# esp8266-hw8.net
KiCad netlist of a schematic drawn in EAGLE
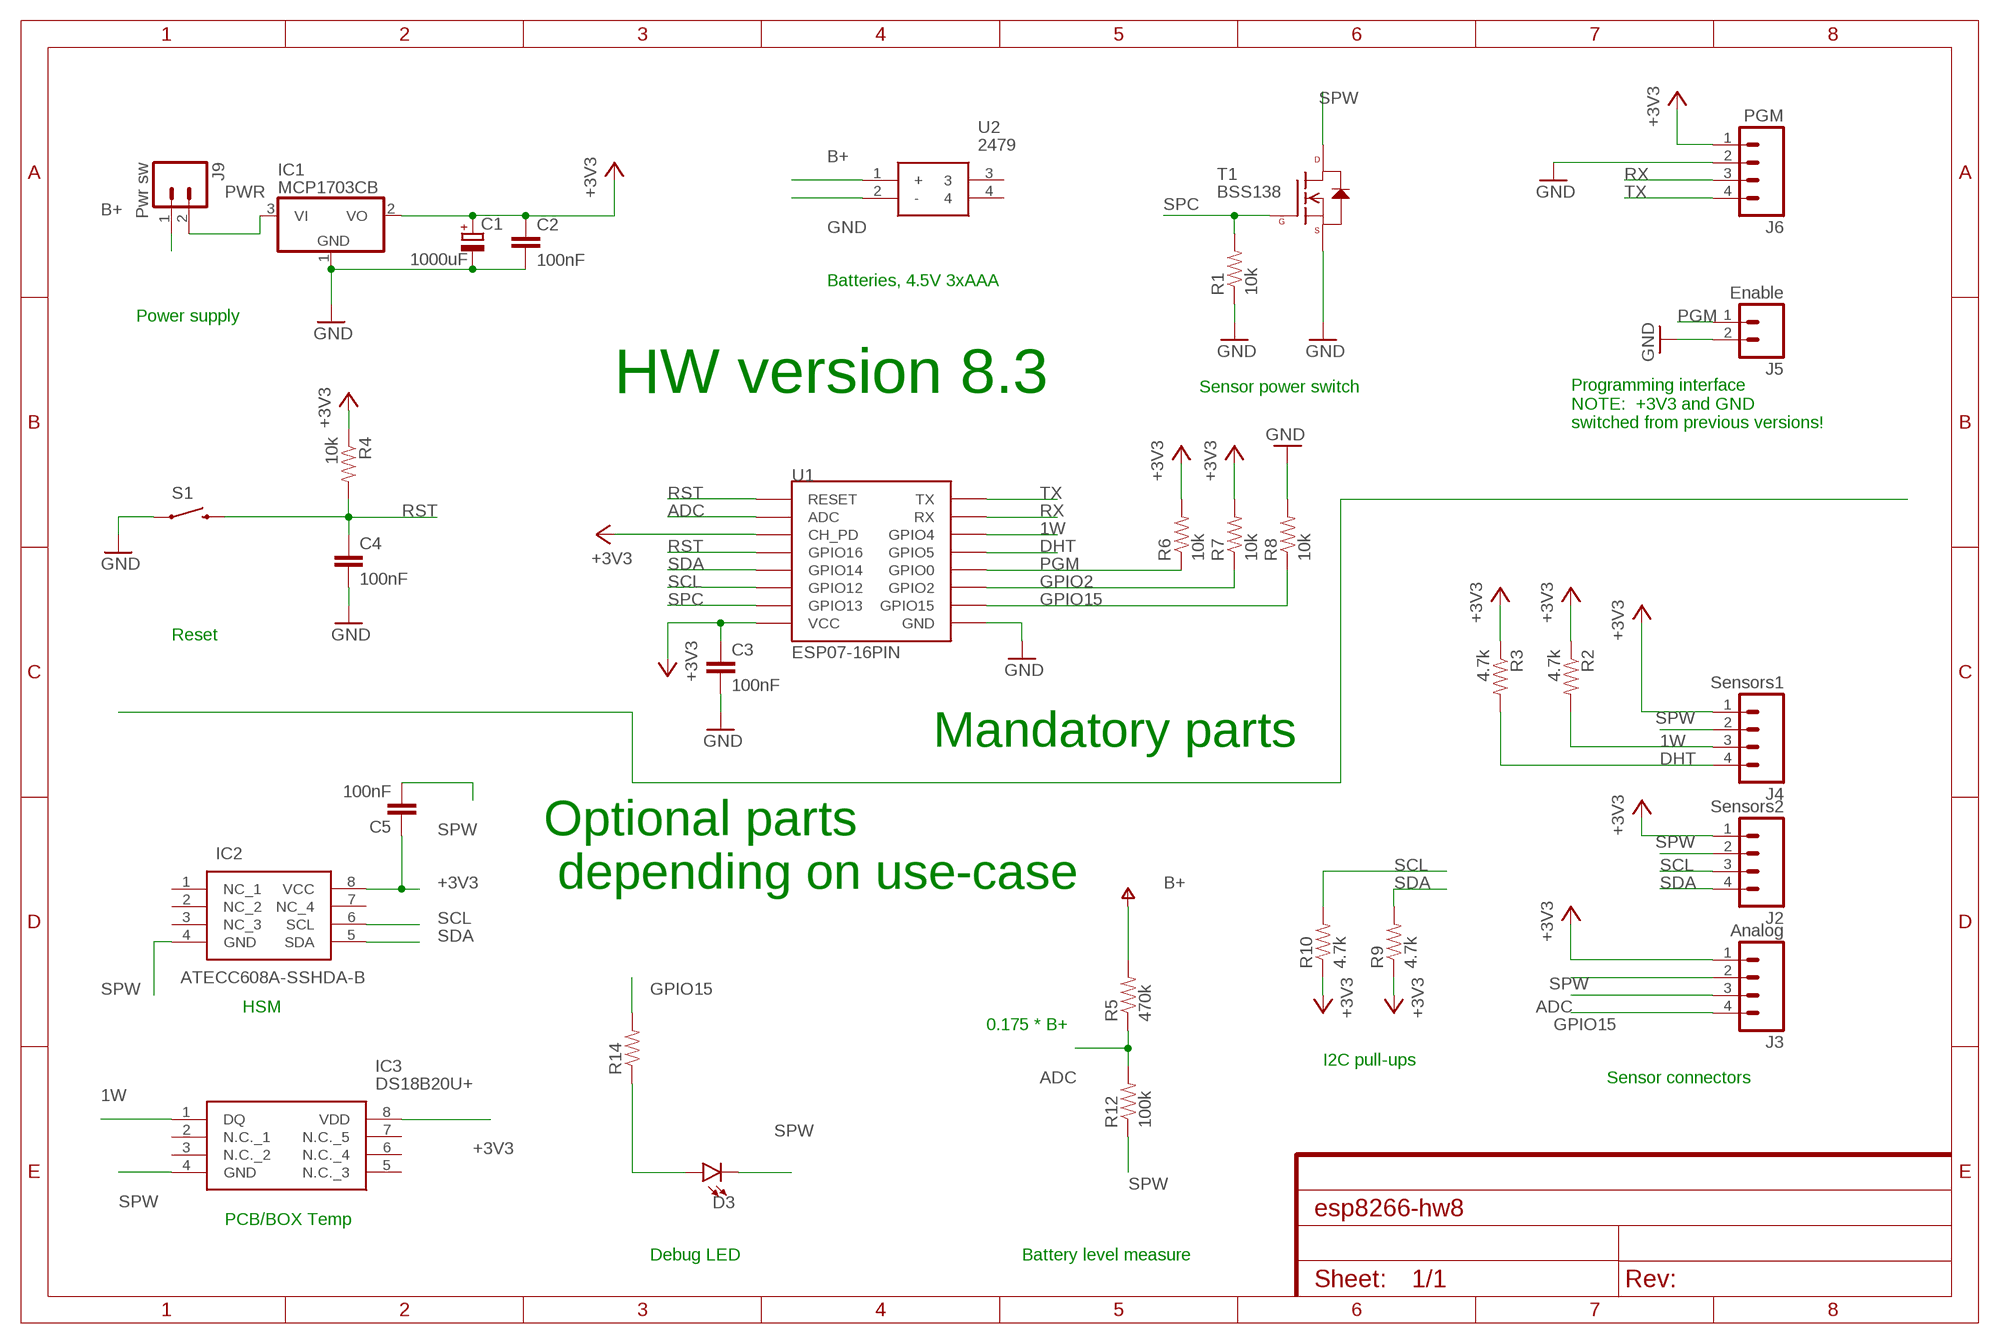
[diagram p0: schematic, sheet 1]

(export (version "E")
  (design (tool "Eeschema 10.0.6"))
  (components
    (comp (ref "C1")
      (value "1000uF")
      (footprint "eagle-import:E3,5-8")
      (libsource (lib "eagle-import") (part "CPOL-EUE3.5-8"))
    )
    (comp (ref "C2")
      (value "100nF")
      (footprint "eagle-import:0805")
      (libsource (lib "eagle-import") (part "CAP0805"))
    )
    (comp (ref "C3")
      (value "100nF")
      (footprint "eagle-import:0805")
      (libsource (lib "eagle-import") (part "CAP0805"))
    )
    (comp (ref "C4")
      (value "100nF")
      (footprint "eagle-import:0805")
      (libsource (lib "eagle-import") (part "CAP0805"))
    )
    (comp (ref "C5")
      (value "100nF")
      (footprint "eagle-import:0805")
      (libsource (lib "eagle-import") (part "CAP0805"))
    )
    (comp (ref "D3")
      (value "LED3MM")
      (footprint "eagle-import:LED_3MM")
      (libsource (lib "eagle-import") (part "LED3MM"))
    )
    (comp (ref "IC1")
      (value "MCP1703CB")
      (footprint "eagle-import:SOT23")
      (libsource (lib "eagle-import") (part "MCP1703CB"))
    )
    (comp (ref "IC2")
      (value "ATECC608A-SSHDA-B")
      (footprint "eagle-import:SOIC127P600X175-8N")
      (fields (field (name "MOUSER_PART_NUMBER") "556-ATECC608ASSHDAB"))
      (libsource (lib "eagle-import") (part "ATECC608A-SSHDA-B"))
    )
    (comp (ref "IC3")
      (value "DS18B20U+")
      (footprint "eagle-import:SOP65P490X110-8N")
      (fields (field (name "MOUSER_PART_NUMBER") "700-DS18B20U"))
      (libsource (lib "eagle-import") (part "DS18B20U+"))
    )
    (comp (ref "J2")
      (value "Sensors2")
      (footprint "eagle-import:1X04")
      (libsource (lib "eagle-import") (part "M04PTH"))
    )
    (comp (ref "J3")
      (value "Analog")
      (footprint "eagle-import:1X04")
      (libsource (lib "eagle-import") (part "M04PTH"))
    )
    (comp (ref "J4")
      (value "Sensors1")
      (footprint "eagle-import:1X04")
      (libsource (lib "eagle-import") (part "M04PTH"))
    )
    (comp (ref "J5")
      (value "Enable")
      (footprint "eagle-import:1X02")
      (libsource (lib "eagle-import") (part "M02PTH"))
    )
    (comp (ref "J6")
      (value "PGM")
      (footprint "eagle-import:1X04")
      (libsource (lib "eagle-import") (part "M04PTH"))
    )
    (comp (ref "J9")
      (value "Pwr sw")
      (footprint "eagle-import:1X02")
      (libsource (lib "eagle-import") (part "M02PTH"))
    )
    (comp (ref "R1")
      (value "10k")
      (footprint "eagle-import:0805")
      (libsource (lib "eagle-import") (part "RESISTOR0805-RES"))
    )
    (comp (ref "R2")
      (value "4.7k")
      (footprint "eagle-import:0805")
      (libsource (lib "eagle-import") (part "RESISTOR0805-RES"))
    )
    (comp (ref "R3")
      (value "4.7k")
      (footprint "eagle-import:0805")
      (libsource (lib "eagle-import") (part "RESISTOR0805-RES"))
    )
    (comp (ref "R4")
      (value "10k")
      (footprint "eagle-import:0805")
      (libsource (lib "eagle-import") (part "RESISTOR0805-RES"))
    )
    (comp (ref "R5")
      (value "470k")
      (footprint "eagle-import:0805")
      (libsource (lib "eagle-import") (part "RESISTOR0805-RES"))
    )
    (comp (ref "R6")
      (value "10k")
      (footprint "eagle-import:0805")
      (libsource (lib "eagle-import") (part "RESISTOR0805-RES"))
    )
    (comp (ref "R7")
      (value "10k")
      (footprint "eagle-import:0805")
      (libsource (lib "eagle-import") (part "RESISTOR0805-RES"))
    )
    (comp (ref "R8")
      (value "10k")
      (footprint "eagle-import:0805")
      (libsource (lib "eagle-import") (part "RESISTOR0805-RES"))
    )
    (comp (ref "R9")
      (value "4.7k")
      (footprint "eagle-import:0805")
      (libsource (lib "eagle-import") (part "RESISTOR0805-RES"))
    )
    (comp (ref "R10")
      (value "4.7k")
      (footprint "eagle-import:0805")
      (libsource (lib "eagle-import") (part "RESISTOR0805-RES"))
    )
    (comp (ref "R12")
      (value "100k")
      (footprint "eagle-import:0805")
      (libsource (lib "eagle-import") (part "RESISTOR0805-RES"))
    )
    (comp (ref "R14")
      (value "470")
      (footprint "eagle-import:0805")
      (libsource (lib "eagle-import") (part "RESISTOR0805-RES"))
    )
    (comp (ref "S1")
      (value "RESET")
      (footprint "eagle-import:TACTILE-SWITCH-1101NE")
      (libsource (lib "eagle-import") (part "SWITCH-MOMENTARY-2SMD-1101NE"))
    )
    (comp (ref "T1")
      (value "BSS138")
      (footprint "eagle-import:SOT23-3")
      (libsource (lib "eagle-import") (part "N-CHANNEL-MOSFET-BSS138"))
    )
    (comp (ref "U1")
      (value "ESP07-16PIN")
      (footprint "eagle-import:ESP07-16PIN")
      (libsource (lib "eagle-import") (part "ESP07-16PIN"))
    )
    (comp (ref "U2")
      (value "2479")
      (footprint "eagle-import:2479")
      (fields (field (name "MOUSER_PART_NUMBER") "534-2479"))
      (libsource (lib "eagle-import") (part "2479"))
    )
  )
  (nets
    (net (code "1") (name "+3V3") (class "Default")
      (node (ref "C1") (pin "+") (pinfunction "+_+") (pintype "passive"))
      (node (ref "C2") (pin "1") (pinfunction "1_1") (pintype "passive"))
      (node (ref "C3") (pin "1") (pinfunction "1_1") (pintype "passive"))
      (node (ref "C5") (pin "1") (pinfunction "1_1") (pintype "passive"))
      (node (ref "IC1") (pin "2") (pinfunction "VO_2") (pintype "passive"))
      (node (ref "IC2") (pin "8") (pinfunction "VCC_8") (pintype "bidirectional"))
      (node (ref "IC3") (pin "8") (pinfunction "VDD_8") (pintype "power_in"))
      (node (ref "J2") (pin "1") (pinfunction "1_1") (pintype "passive"))
      (node (ref "J3") (pin "1") (pinfunction "1_1") (pintype "passive"))
      (node (ref "J4") (pin "1") (pinfunction "1_1") (pintype "passive"))
      (node (ref "J6") (pin "1") (pinfunction "1_1") (pintype "passive"))
      (node (ref "R10") (pin "1") (pinfunction "1_1") (pintype "passive"))
      (node (ref "R2") (pin "1") (pinfunction "1_1") (pintype "passive"))
      (node (ref "R3") (pin "1") (pinfunction "1_1") (pintype "passive"))
      (node (ref "R4") (pin "1") (pinfunction "1_1") (pintype "passive"))
      (node (ref "R6") (pin "2") (pinfunction "2_2") (pintype "passive"))
      (node (ref "R7") (pin "2") (pinfunction "2_2") (pintype "passive"))
      (node (ref "R9") (pin "1") (pinfunction "1_1") (pintype "passive"))
      (node (ref "U1") (pin "CH_PD") (pinfunction "CH_PD_CH_PD") (pintype "bidirectional"))
      (node (ref "U1") (pin "VCC") (pinfunction "VCC_VCC") (pintype "bidirectional"))
    )
    (net (code "2") (name "/1W") (class "Default")
      (node (ref "IC3") (pin "1") (pinfunction "DQ_1") (pintype "bidirectional"))
      (node (ref "J4") (pin "3") (pinfunction "3_3") (pintype "passive"))
      (node (ref "R2") (pin "2") (pinfunction "2_2") (pintype "passive"))
      (node (ref "U1") (pin "GPIO4") (pinfunction "GPIO4_GPIO4") (pintype "bidirectional"))
    )
    (net (code "3") (name "/ADC") (class "Default")
      (node (ref "J3") (pin "3") (pinfunction "3_3") (pintype "passive"))
      (node (ref "R12") (pin "2") (pinfunction "2_2") (pintype "passive"))
      (node (ref "R5") (pin "1") (pinfunction "1_1") (pintype "passive"))
      (node (ref "U1") (pin "ADC") (pinfunction "ADC_ADC") (pintype "bidirectional"))
    )
    (net (code "4") (name "/DHT") (class "Default")
      (node (ref "J4") (pin "4") (pinfunction "4_4") (pintype "passive"))
      (node (ref "R3") (pin "2") (pinfunction "2_2") (pintype "passive"))
      (node (ref "U1") (pin "GPIO5") (pinfunction "GPIO5_GPIO5") (pintype "bidirectional"))
    )
    (net (code "5") (name "/GPIO2") (class "Default")
      (node (ref "R7") (pin "1") (pinfunction "1_1") (pintype "passive"))
      (node (ref "U1") (pin "GPIO2") (pinfunction "GPIO2_GPIO2") (pintype "bidirectional"))
    )
    (net (code "6") (name "/GPIO15") (class "Default")
      (node (ref "J3") (pin "4") (pinfunction "4_4") (pintype "passive"))
      (node (ref "R14") (pin "2") (pinfunction "2_2") (pintype "passive"))
      (node (ref "R8") (pin "1") (pinfunction "1_1") (pintype "passive"))
      (node (ref "U1") (pin "GPIO15") (pinfunction "GPIO15_GPIO15") (pintype "bidirectional"))
    )
    (net (code "7") (name "/PGM") (class "Default")
      (node (ref "J5") (pin "1") (pinfunction "1_1") (pintype "passive"))
      (node (ref "R6") (pin "1") (pinfunction "1_1") (pintype "passive"))
      (node (ref "U1") (pin "GPIO0") (pinfunction "GPIO0_GPIO0") (pintype "bidirectional"))
    )
    (net (code "8") (name "/PWR") (class "Default")
      (node (ref "IC1") (pin "3") (pinfunction "VI_3") (pintype "input"))
      (node (ref "J9") (pin "2") (pinfunction "2_2") (pintype "passive"))
    )
    (net (code "9") (name "/RST") (class "Default")
      (node (ref "C4") (pin "1") (pinfunction "1_1") (pintype "passive"))
      (node (ref "R4") (pin "2") (pinfunction "2_2") (pintype "passive"))
      (node (ref "S1") (pin "2") (pinfunction "2_2") (pintype "passive"))
      (node (ref "U1") (pin "GPIO16") (pinfunction "GPIO16_GPIO16") (pintype "bidirectional"))
      (node (ref "U1") (pin "REST") (pinfunction "RESET_REST") (pintype "bidirectional"))
    )
    (net (code "10") (name "/RX") (class "Default")
      (node (ref "J6") (pin "3") (pinfunction "3_3") (pintype "passive"))
      (node (ref "U1") (pin "RX") (pinfunction "RX_RX") (pintype "bidirectional"))
    )
    (net (code "11") (name "/SCL") (class "Default")
      (node (ref "IC2") (pin "6") (pinfunction "SCL_6") (pintype "bidirectional"))
      (node (ref "J2") (pin "3") (pinfunction "3_3") (pintype "passive"))
      (node (ref "R10") (pin "2") (pinfunction "2_2") (pintype "passive"))
      (node (ref "U1") (pin "GPIO12") (pinfunction "GPIO12_GPIO12") (pintype "bidirectional"))
    )
    (net (code "12") (name "/SDA") (class "Default")
      (node (ref "IC2") (pin "5") (pinfunction "SDA_5") (pintype "bidirectional"))
      (node (ref "J2") (pin "4") (pinfunction "4_4") (pintype "passive"))
      (node (ref "R9") (pin "2") (pinfunction "2_2") (pintype "passive"))
      (node (ref "U1") (pin "GPIO14") (pinfunction "GPIO14_GPIO14") (pintype "bidirectional"))
    )
    (net (code "13") (name "/SPC") (class "Default")
      (node (ref "R1") (pin "2") (pinfunction "2_2") (pintype "passive"))
      (node (ref "T1") (pin "1") (pinfunction "G_1") (pintype "passive"))
      (node (ref "U1") (pin "GPIO13") (pinfunction "GPIO13_GPIO13") (pintype "bidirectional"))
    )
    (net (code "14") (name "/SPW") (class "Default")
      (node (ref "C5") (pin "2") (pinfunction "2_2") (pintype "passive"))
      (node (ref "D3") (pin "K") (pinfunction "C_K") (pintype "passive"))
      (node (ref "IC2") (pin "4") (pinfunction "GND_4") (pintype "bidirectional"))
      (node (ref "IC3") (pin "4") (pinfunction "GND_4") (pintype "power_in"))
      (node (ref "J2") (pin "2") (pinfunction "2_2") (pintype "passive"))
      (node (ref "J3") (pin "2") (pinfunction "2_2") (pintype "passive"))
      (node (ref "J4") (pin "2") (pinfunction "2_2") (pintype "passive"))
      (node (ref "R12") (pin "1") (pinfunction "1_1") (pintype "passive"))
      (node (ref "T1") (pin "3") (pinfunction "D_3") (pintype "passive"))
    )
    (net (code "15") (name "/TX") (class "Default")
      (node (ref "J6") (pin "4") (pinfunction "4_4") (pintype "passive"))
      (node (ref "U1") (pin "TX") (pinfunction "TX_TX") (pintype "bidirectional"))
    )
    (net (code "16") (name "GND") (class "Default")
      (node (ref "C1") (pin "-") (pinfunction "-_-") (pintype "passive"))
      (node (ref "C2") (pin "2") (pinfunction "2_2") (pintype "passive"))
      (node (ref "C3") (pin "2") (pinfunction "2_2") (pintype "passive"))
      (node (ref "C4") (pin "2") (pinfunction "2_2") (pintype "passive"))
      (node (ref "IC1") (pin "1") (pinfunction "GND_1") (pintype "passive"))
      (node (ref "J5") (pin "2") (pinfunction "2_2") (pintype "passive"))
      (node (ref "J6") (pin "2") (pinfunction "2_2") (pintype "passive"))
      (node (ref "R1") (pin "1") (pinfunction "1_1") (pintype "passive"))
      (node (ref "R8") (pin "2") (pinfunction "2_2") (pintype "passive"))
      (node (ref "S1") (pin "1") (pinfunction "1_1") (pintype "passive"))
      (node (ref "T1") (pin "2") (pinfunction "S_2") (pintype "passive"))
      (node (ref "U1") (pin "GND") (pinfunction "GND_GND") (pintype "bidirectional"))
      (node (ref "U2") (pin "2") (pinfunction "-_2") (pintype "bidirectional"))
    )
    (net (code "17") (name "Net-(D3-PadA)") (class "Default")
      (node (ref "D3") (pin "A") (pinfunction "A_A") (pintype "passive"))
      (node (ref "R14") (pin "1") (pinfunction "1_1") (pintype "passive"))
    )
    (net (code "18") (name "V+") (class "Default")
      (node (ref "J9") (pin "1") (pinfunction "1_1") (pintype "passive"))
      (node (ref "R5") (pin "2") (pinfunction "2_2") (pintype "passive"))
      (node (ref "U2") (pin "1") (pinfunction "+_1") (pintype "bidirectional"))
    )
    (net (code "19") (name "unconnected-(IC2-NC_1-Pad1)") (class "Default")
      (node (ref "IC2") (pin "1") (pinfunction "NC_1_1") (pintype "bidirectional"))
    )
    (net (code "20") (name "unconnected-(IC2-NC_2-Pad2)") (class "Default")
      (node (ref "IC2") (pin "2") (pinfunction "NC_2_2") (pintype "bidirectional"))
    )
    (net (code "21") (name "unconnected-(IC2-NC_3-Pad3)") (class "Default")
      (node (ref "IC2") (pin "3") (pinfunction "NC_3_3") (pintype "bidirectional"))
    )
    (net (code "22") (name "unconnected-(IC2-NC_4-Pad7)") (class "Default")
      (node (ref "IC2") (pin "7") (pinfunction "NC_4_7") (pintype "bidirectional"))
    )
    (net (code "23") (name "unconnected-(IC3-N.C._1-Pad2)") (class "Default")
      (node (ref "IC3") (pin "2") (pinfunction "N.C._1_2") (pintype "bidirectional"))
    )
    (net (code "24") (name "unconnected-(IC3-N.C._2-Pad3)") (class "Default")
      (node (ref "IC3") (pin "3") (pinfunction "N.C._2_3") (pintype "bidirectional"))
    )
    (net (code "25") (name "unconnected-(IC3-N.C._3-Pad5)") (class "Default")
      (node (ref "IC3") (pin "5") (pinfunction "N.C._3_5") (pintype "bidirectional"))
    )
    (net (code "26") (name "unconnected-(IC3-N.C._4-Pad6)") (class "Default")
      (node (ref "IC3") (pin "6") (pinfunction "N.C._4_6") (pintype "bidirectional"))
    )
    (net (code "27") (name "unconnected-(IC3-N.C._5-Pad7)") (class "Default")
      (node (ref "IC3") (pin "7") (pinfunction "N.C._5_7") (pintype "bidirectional"))
    )
    (net (code "28") (name "unconnected-(U2-Pad3)") (class "Default")
      (node (ref "U2") (pin "3") (pinfunction "3_3") (pintype "bidirectional"))
    )
    (net (code "29") (name "unconnected-(U2-Pad4)") (class "Default")
      (node (ref "U2") (pin "4") (pinfunction "4_4") (pintype "bidirectional"))
    )
  )
)
